# MSP-EXP430F5529LP_0.net
KiCad netlist of a schematic drawn in Altium Designer
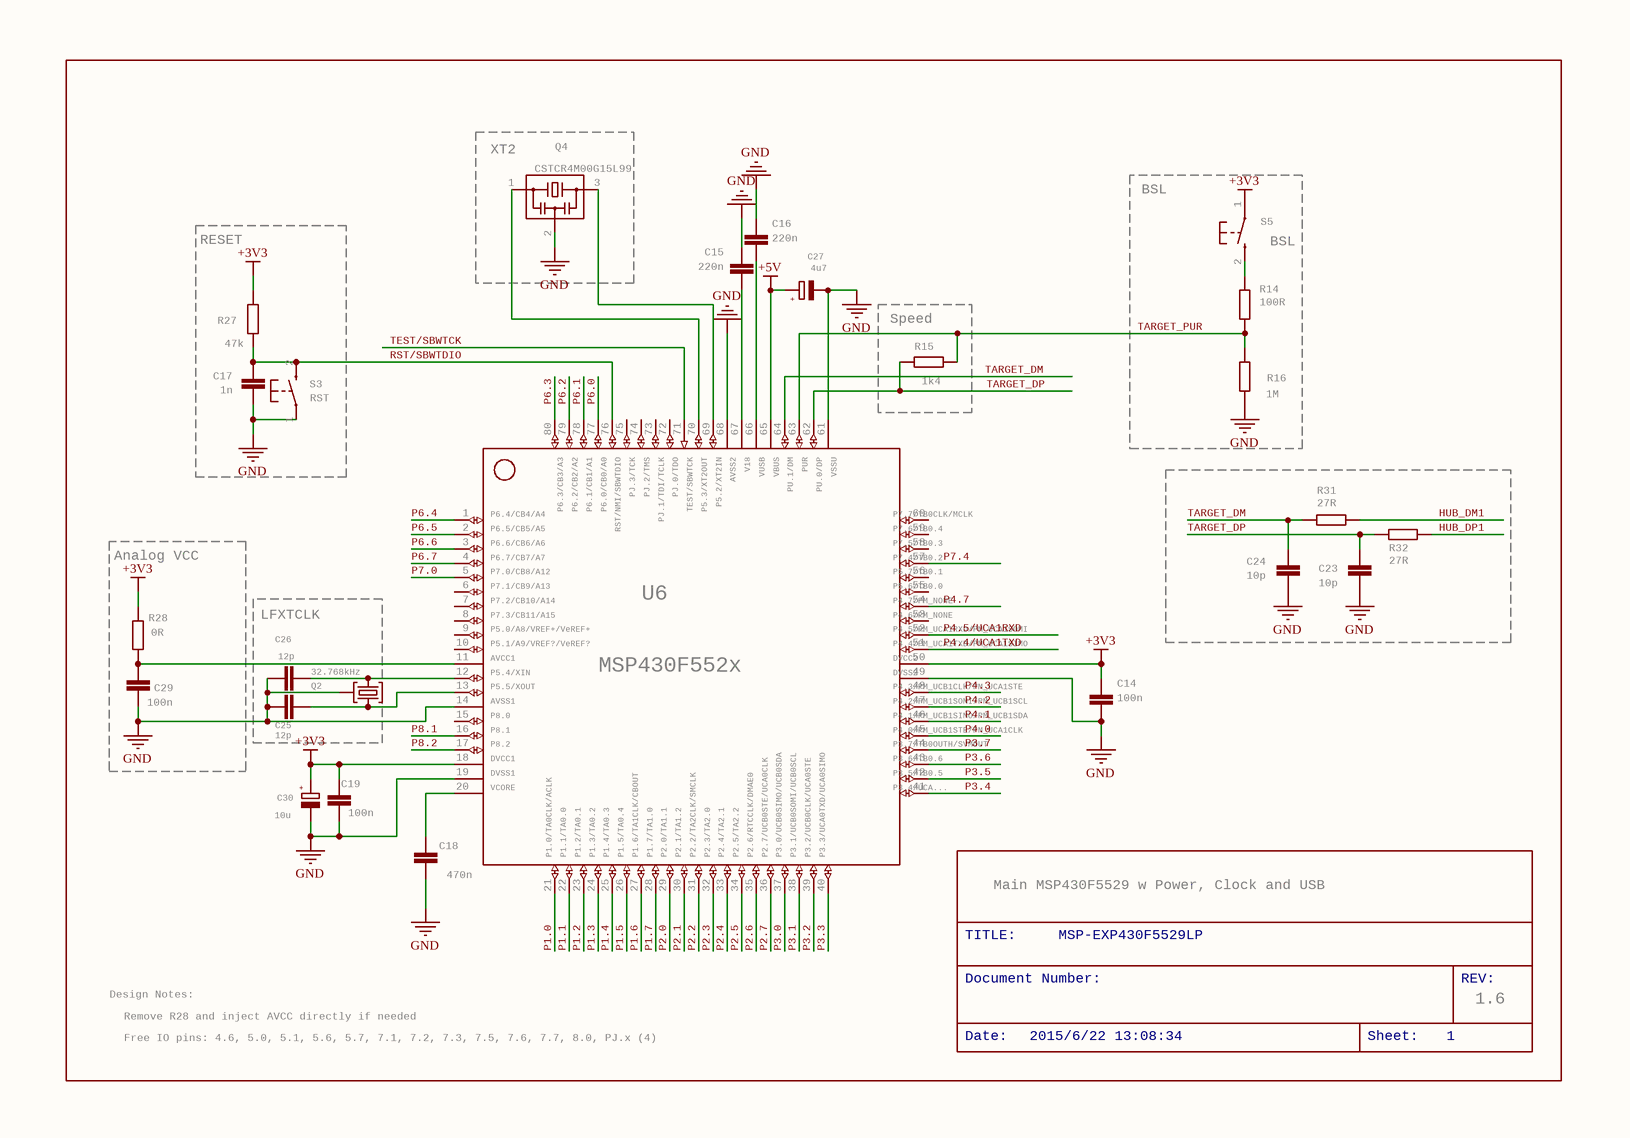
[diagram p0: MSP-EXP430F5529LP_0.SchDoc]

(export (version "E")
  (design (tool "Eeschema 10.0.6"))
  (components
    (comp (ref "C14")
      (value "100n")
      (footprint "0402")
      (description "CAPACITOR, European symbol")
      (libsource (lib "") (part "C-EUCM0402_1"))
    )
    (comp (ref "C15")
      (value "220n")
      (footprint "0402")
      (description "CAPACITOR, European symbol")
      (libsource (lib "") (part "C-EUCM0402_2"))
    )
    (comp (ref "C16")
      (value "220n")
      (footprint "0402")
      (description "CAPACITOR, European symbol")
      (libsource (lib "rcl") (part "C-EUCM0402"))
    )
    (comp (ref "C17")
      (value "1n")
      (footprint "0402")
      (description "CAPACITOR, European symbol")
      (libsource (lib "") (part "C-EUCM0402_1"))
    )
    (comp (ref "C18")
      (value "470n")
      (footprint "0402")
      (description "CAPACITOR, European symbol")
      (libsource (lib "rcl") (part "C-EUCM0402"))
    )
    (comp (ref "C19")
      (value "100n")
      (footprint "0402")
      (description "CAPACITOR, European symbol")
      (libsource (lib "rcl") (part "C-EUCM0402"))
    )
    (comp (ref "C23")
      (value "10p")
      (footprint "0402")
      (description "CAPACITOR, European symbol")
      (libsource (lib "") (part "C-EUCM0402_1"))
    )
    (comp (ref "C24")
      (value "10p")
      (footprint "0402")
      (description "CAPACITOR, European symbol")
      (libsource (lib "") (part "C-EUCM0402_1"))
    )
    (comp (ref "C25")
      (value "12p")
      (footprint "0402")
      (description "CAPACITOR, European symbol")
      (libsource (lib "") (part "C-EUCM0402_2"))
    )
    (comp (ref "C26")
      (value "12p")
      (footprint "0402")
      (description "CAPACITOR, European symbol")
      (libsource (lib "") (part "C-EUCM0402_2"))
    )
    (comp (ref "C27")
      (value "4u7")
      (footprint "A/3216-18R")
      (description "POLARIZED CAPACITOR, European symbol")
      (fields (field (name "+") "+"))
      (libsource (lib "") (part "CPOL-EUA/3216-18R_1"))
    )
    (comp (ref "C29")
      (value "100n")
      (footprint "0402")
      (description "CAPACITOR, European symbol")
      (libsource (lib "") (part "C-EUCM0402_3"))
    )
    (comp (ref "C30")
      (value "10u")
      (footprint "A/3216-18R")
      (description "POLARIZED CAPACITOR, European symbol")
      (fields (field (name "+") "+"))
      (libsource (lib "rcl") (part "CPOL-EUA/3216-18R"))
    )
    (comp (ref "Q2")
      (value "32.768kHz")
      (footprint "MS3V-T1R")
      (fields (field (name "LIBRARYNAME") "microcrystal"))
      (libsource (lib "microcrystal") (part "MS3V-T1R"))
    )
    (comp (ref "Q4")
      (value "CSTCR4M00G15L99")
      (footprint "MURATA-FILTER_CSTCR")
      (description "Resonator   Source: murata.co.jp")
      (fields (field (name "MF") "MF") (field (name "MPN") "CSTCR6M00G53-R0"))
      (libsource (lib "murata") (part "MURATA-FILTER_CSTCR"))
    )
    (comp (ref "R14")
      (value "100R")
      (footprint "0402")
      (description "RESISTOR, European symbol")
      (libsource (lib "rcl") (part "R-EU_RM0402"))
    )
    (comp (ref "R15")
      (value "1k4")
      (footprint "0402")
      (description "RESISTOR, European symbol")
      (libsource (lib "rcl") (part "R-EU_RM0402"))
    )
    (comp (ref "R16")
      (value "1M")
      (footprint "0402")
      (description "RESISTOR, European symbol")
      (libsource (lib "rcl") (part "R-EU_RM0402"))
    )
    (comp (ref "R27")
      (value "47k")
      (footprint "0402")
      (description "RESISTOR, European symbol")
      (libsource (lib "rcl") (part "R-EU_RM0402"))
    )
    (comp (ref "R28")
      (value "0R")
      (footprint "0402")
      (description "RESISTOR, European symbol")
      (libsource (lib "rcl") (part "R-EU_RM0402"))
    )
    (comp (ref "R31")
      (value "27R")
      (footprint "0402")
      (description "RESISTOR, European symbol")
      (libsource (lib "rcl") (part "R-EU_RM0402"))
    )
    (comp (ref "R32")
      (value "27R")
      (footprint "0402")
      (description "RESISTOR, European symbol")
      (libsource (lib "rcl") (part "R-EU_RM0402"))
    )
    (comp (ref "S3")
      (value "RST")
      (footprint "PBTH")
      (description "OMRON SWITCH")
      (fields (field (name "LIBRARYNAME") "electricalmeter"))
      (libsource (lib "electricalmeter") (part "PB"))
    )
    (comp (ref "S5")
      (value "BSL")
      (footprint "PBTH")
      (description "OMRON SWITCH")
      (fields (field (name "LIBRARYNAME") "electricalmeter"))
      (libsource (lib "electricalmeter") (part "PB"))
    )
    (comp (ref "U6")
      (value "MSP430F5529IPNR")
      (footprint "PN80")
      (fields
        (field (name "P6.3/CB3/A3") "P6.3/CB3/A3")
        (field (name "P6.2/CB2/A2") "P6.2/CB2/A2")
        (field (name "P6.1/CB1/A1") "P6.1/CB1/A1")
        (field (name "P6.0/CB0/A0") "P6.0/CB0/A0")
        (field (name "PJ.3/TCK") "PJ.3/TCK")
        (field (name "PJ.2/TMS") "PJ.2/TMS")
        (field (name "PJ.1/TDI/TCLK") "PJ.1/TDI/TCLK")
        (field (name "PJ.0/TDO") "PJ.0/TDO")
        (field (name "TEST/SBWTCK") "TEST/SBWTCK")
        (field (name "P5.3/XT2OUT") "P5.3/XT2OUT")
        (field (name "P5.2/XT2IN") "P5.2/XT2IN")
        (field (name "AVSS2") "AVSS2")
        (field (name "V18") "V18")
        (field (name "VUSB") "VUSB")
        (field (name "VBUS") "VBUS")
        (field (name "PU.1/DM") "PU.1/DM")
        (field (name "PUR") "PUR")
        (field (name "PU.0/DP") "PU.0/DP")
        (field (name "VSSU") "VSSU")
        (field (name "RST/NMI/SBWTDIO") "RST/NMI/SBWTDIO")
        (field (name "P7.7/TB0CLK/MCLK") "P7.7/TB0CLK/MCLK")
        (field (name "P7.6/TB0.4") "P7.6/TB0.4")
        (field (name "P7.5/TB0.3") "P7.5/TB0.3")
        (field (name "P7.4/TB0.2") "P7.4/TB0.2")
        (field (name "P5.7/TB0.1") "P5.7/TB0.1")
        (field (name "P5.6/TB0.0") "P5.6/TB0.0")
        (field (name "P4.7/PM_NONE") "P4.7/PM_NONE")
        (field (name "P4.5/PM_UCA1RXD/PM_UCA1SOMI") "P4.5/PM_UCA1RXD/PM_UCA1SOMI")
        (field (name "P4.4/PM_UCA1TXD/PM_UCA1SIMO") "P4.4/PM_UCA1TXD/PM_UCA1SIMO")
        (field (name "DVCC2") "DVCC2")
        (field (name "P4.3/PM_UCB1CLK/PM_UCA1STE") "P4.3/PM_UCB1CLK/PM_UCA1STE")
        (field (name "P4.2/PM_UCB1SOMI/PM_UCB1SCL") "P4.2/PM_UCB1SOMI/PM_UCB1SCL")
        (field (name "P4.1/PM_UCB1SIMO/PM_UCB1SDA") "P4.1/PM_UCB1SIMO/PM_UCB1SDA")
        (field (name "P4.0/PM_UCB1STE/PM_UCA1CLK") "P4.0/PM_UCB1STE/PM_UCA1CLK")
        (field (name "P3.7/TB0OUTH/SVMOUT") "P3.7/TB0OUTH/SVMOUT")
        (field (name "P3.6/TB0.6") "P3.6/TB0.6")
        (field (name "P4.6/PM_NONE") "P4.6/PM_NONE")
        (field (name "P3.5/TB0.5") "P3.5/TB0.5")
        (field (name "P3.4/UCA...") "P3.4/UCA...")
        (field (name "P1.0/TA0CLK/ACLK") "P1.0/TA0CLK/ACLK")
        (field (name "P1.1/TA0.0") "P1.1/TA0.0")
        (field (name "P1.2/TA0.1") "P1.2/TA0.1")
        (field (name "P1.3/TA0.2") "P1.3/TA0.2")
        (field (name "P1.4/TA0.3") "P1.4/TA0.3")
        (field (name "P1.5/TA0.4") "P1.5/TA0.4")
        (field (name "P1.6/TA1CLK/CBOUT") "P1.6/TA1CLK/CBOUT")
        (field (name "P1.7/TA1.0") "P1.7/TA1.0")
        (field (name "P2.0/TA1.1") "P2.0/TA1.1")
        (field (name "P2.1/TA1.2") "P2.1/TA1.2")
        (field (name "P2.2/TA2CLK/SMCLK") "P2.2/TA2CLK/SMCLK")
        (field (name "P2.4/TA2.1") "P2.4/TA2.1")
        (field (name "P2.5/TA2.2") "P2.5/TA2.2")
        (field (name "P2.6/RTCCLK/DMAE0") "P2.6/RTCCLK/DMAE0")
        (field (name "P2.7/UCB0STE/UCA0CLK") "P2.7/UCB0STE/UCA0CLK")
        (field (name "P3.0/UCB0SIMO/UCB0SDA") "P3.0/UCB0SIMO/UCB0SDA")
        (field (name "P3.1/UCB0SOMI/UCB0SCL") "P3.1/UCB0SOMI/UCB0SCL")
        (field (name "P3.2/UCB0CLK/UCA0STE") "P3.2/UCB0CLK/UCA0STE")
        (field (name "P3.3/UCA0TXD/UCA0SIMO") "P3.3/UCA0TXD/UCA0SIMO")
        (field (name "P6.4/CB4/A4") "P6.4/CB4/A4")
        (field (name "P6.5/CB5/A5") "P6.5/CB5/A5")
        (field (name "P6.6/CB6/A6") "P6.6/CB6/A6")
        (field (name "P6.7/CB7/A7") "P6.7/CB7/A7")
        (field (name "P7.0/CB8/A12") "P7.0/CB8/A12")
        (field (name "P7.1/CB9/A13") "P7.1/CB9/A13")
        (field (name "P7.2/CB10/A14") "P7.2/CB10/A14")
        (field (name "P7.3/CB11/A15") "P7.3/CB11/A15")
        (field (name "P5.0/A8/VREF+/VEREF+") "P5.0/A8/VREF+/VeREF+")
        (field (name "P5.1/A9/VREF?/VEREF?") "P5.1/A9/VREF?/VeREF?")
        (field (name "AVCC1") "AVCC1")
        (field (name "P5.4/XIN") "P5.4/XIN")
        (field (name "P5.5/XOUT") "P5.5/XOUT")
        (field (name "AVSS1") "AVSS1")
        (field (name "P8.0") "P8.0")
        (field (name "P8.1") "P8.1")
        (field (name "P8.2") "P8.2")
        (field (name "DVCC1") "DVCC1")
        (field (name "DVSS1") "DVSS1")
        (field (name "VCORE") "VCORE")
        (field (name "MSP430F552X") "MSP430F552x")
        (field (name "DVSS2") "DVSS2")
        (field (name "P2.3/TA2.0") "P2.3/TA2.0")
        (field (name "LIBRARYNAME") "TI_MSP430_v16_intern")
      )
      (libsource (lib "TI_MSP430_v16_intern") (part "F552X---PN80"))
    )
  )
  (nets
    (net (code "1") (name "+3V3") (class "Default")
      (node (ref "C14") (pin "1") (pinfunction "1_1") (pintype "passive"))
      (node (ref "C19") (pin "2") (pinfunction "2_2") (pintype "passive"))
      (node (ref "C30") (pin "+") (pinfunction "+_+") (pintype "passive"))
      (node (ref "R27") (pin "2") (pinfunction "2_2") (pintype "passive"))
      (node (ref "R28") (pin "2") (pinfunction "2_2") (pintype "passive"))
      (node (ref "S5") (pin "1") (pinfunction "P_1") (pintype "passive"))
      (node (ref "U6") (pin "18") (pinfunction "18_18") (pintype "power_in"))
      (node (ref "U6") (pin "50") (pinfunction "50_50") (pintype "power_in"))
    )
    (net (code "2") (name "+5V") (class "Default")
      (node (ref "C27") (pin "+") (pinfunction "+_+") (pintype "passive"))
      (node (ref "U6") (pin "65") (pinfunction "65_65") (pintype "power_in"))
    )
    (net (code "3") (name "/HUB_DM1") (class "Default")
      (node (ref "R31") (pin "1") (pinfunction "1_1") (pintype "passive"))
    )
    (net (code "4") (name "/HUB_DP1") (class "Default")
      (node (ref "R32") (pin "1") (pinfunction "1_1") (pintype "passive"))
    )
    (net (code "5") (name "/P1.0") (class "Default")
      (node (ref "U6") (pin "21") (pinfunction "21_21") (pintype "bidirectional"))
    )
    (net (code "6") (name "/P1.1") (class "Default")
      (node (ref "U6") (pin "22") (pinfunction "22_22") (pintype "bidirectional"))
    )
    (net (code "7") (name "/P1.2") (class "Default")
      (node (ref "U6") (pin "23") (pinfunction "23_23") (pintype "bidirectional"))
    )
    (net (code "8") (name "/P1.3") (class "Default")
      (node (ref "U6") (pin "24") (pinfunction "24_24") (pintype "bidirectional"))
    )
    (net (code "9") (name "/P1.4") (class "Default")
      (node (ref "U6") (pin "25") (pinfunction "25_25") (pintype "bidirectional"))
    )
    (net (code "10") (name "/P1.5") (class "Default")
      (node (ref "U6") (pin "26") (pinfunction "26_26") (pintype "bidirectional"))
    )
    (net (code "11") (name "/P1.6") (class "Default")
      (node (ref "U6") (pin "27") (pinfunction "27_27") (pintype "bidirectional"))
    )
    (net (code "12") (name "/P1.7") (class "Default")
      (node (ref "U6") (pin "28") (pinfunction "28_28") (pintype "bidirectional"))
    )
    (net (code "13") (name "/P2.0") (class "Default")
      (node (ref "U6") (pin "29") (pinfunction "29_29") (pintype "bidirectional"))
    )
    (net (code "14") (name "/P2.1") (class "Default")
      (node (ref "U6") (pin "30") (pinfunction "30_30") (pintype "bidirectional"))
    )
    (net (code "15") (name "/P2.2") (class "Default")
      (node (ref "U6") (pin "31") (pinfunction "31_31") (pintype "bidirectional"))
    )
    (net (code "16") (name "/P2.3") (class "Default")
      (node (ref "U6") (pin "32") (pinfunction "32_32") (pintype "bidirectional"))
    )
    (net (code "17") (name "/P2.4") (class "Default")
      (node (ref "U6") (pin "33") (pinfunction "33_33") (pintype "bidirectional"))
    )
    (net (code "18") (name "/P2.5") (class "Default")
      (node (ref "U6") (pin "34") (pinfunction "34_34") (pintype "bidirectional"))
    )
    (net (code "19") (name "/P2.6") (class "Default")
      (node (ref "U6") (pin "35") (pinfunction "35_35") (pintype "bidirectional"))
    )
    (net (code "20") (name "/P2.7") (class "Default")
      (node (ref "U6") (pin "36") (pinfunction "36_36") (pintype "bidirectional"))
    )
    (net (code "21") (name "/P3.0") (class "Default")
      (node (ref "U6") (pin "37") (pinfunction "37_37") (pintype "bidirectional"))
    )
    (net (code "22") (name "/P3.1") (class "Default")
      (node (ref "U6") (pin "38") (pinfunction "38_38") (pintype "bidirectional"))
    )
    (net (code "23") (name "/P3.2") (class "Default")
      (node (ref "U6") (pin "39") (pinfunction "39_39") (pintype "bidirectional"))
    )
    (net (code "24") (name "/P3.3") (class "Default")
      (node (ref "U6") (pin "40") (pinfunction "40_40") (pintype "bidirectional"))
    )
    (net (code "25") (name "/P3.4") (class "Default")
      (node (ref "U6") (pin "41") (pinfunction "41_41") (pintype "bidirectional"))
    )
    (net (code "26") (name "/P3.5") (class "Default")
      (node (ref "U6") (pin "42") (pinfunction "42_42") (pintype "bidirectional"))
    )
    (net (code "27") (name "/P3.6") (class "Default")
      (node (ref "U6") (pin "43") (pinfunction "43_43") (pintype "bidirectional"))
    )
    (net (code "28") (name "/P3.7") (class "Default")
      (node (ref "U6") (pin "44") (pinfunction "44_44") (pintype "bidirectional"))
    )
    (net (code "29") (name "/P4.0") (class "Default")
      (node (ref "U6") (pin "45") (pinfunction "45_45") (pintype "bidirectional"))
    )
    (net (code "30") (name "/P4.1") (class "Default")
      (node (ref "U6") (pin "46") (pinfunction "46_46") (pintype "bidirectional"))
    )
    (net (code "31") (name "/P4.2") (class "Default")
      (node (ref "U6") (pin "47") (pinfunction "47_47") (pintype "bidirectional"))
    )
    (net (code "32") (name "/P4.3") (class "Default")
      (node (ref "U6") (pin "48") (pinfunction "48_48") (pintype "bidirectional"))
    )
    (net (code "33") (name "/P4.4{slash}UCA1TXD") (class "Default")
      (node (ref "U6") (pin "51") (pinfunction "51_51") (pintype "bidirectional"))
    )
    (net (code "34") (name "/P4.5{slash}UCA1RXD") (class "Default")
      (node (ref "U6") (pin "52") (pinfunction "52_52") (pintype "bidirectional"))
    )
    (net (code "35") (name "/P4.7") (class "Default")
      (node (ref "U6") (pin "54") (pinfunction "54_54") (pintype "bidirectional"))
    )
    (net (code "36") (name "/P6.0") (class "Default")
      (node (ref "U6") (pin "77") (pinfunction "77_77") (pintype "bidirectional"))
    )
    (net (code "37") (name "/P6.1") (class "Default")
      (node (ref "U6") (pin "78") (pinfunction "78_78") (pintype "bidirectional"))
    )
    (net (code "38") (name "/P6.2") (class "Default")
      (node (ref "U6") (pin "79") (pinfunction "79_79") (pintype "bidirectional"))
    )
    (net (code "39") (name "/P6.3") (class "Default")
      (node (ref "U6") (pin "80") (pinfunction "80_80") (pintype "bidirectional"))
    )
    (net (code "40") (name "/P6.4") (class "Default")
      (node (ref "U6") (pin "1") (pinfunction "1_1") (pintype "bidirectional"))
    )
    (net (code "41") (name "/P6.5") (class "Default")
      (node (ref "U6") (pin "2") (pinfunction "2_2") (pintype "bidirectional"))
    )
    (net (code "42") (name "/P6.6") (class "Default")
      (node (ref "U6") (pin "3") (pinfunction "3_3") (pintype "bidirectional"))
    )
    (net (code "43") (name "/P6.7") (class "Default")
      (node (ref "U6") (pin "4") (pinfunction "4_4") (pintype "bidirectional"))
    )
    (net (code "44") (name "/P7.0") (class "Default")
      (node (ref "U6") (pin "5") (pinfunction "5_5") (pintype "bidirectional"))
    )
    (net (code "45") (name "/P7.4") (class "Default")
      (node (ref "U6") (pin "57") (pinfunction "57_57") (pintype "bidirectional"))
    )
    (net (code "46") (name "/P8.1") (class "Default")
      (node (ref "U6") (pin "16") (pinfunction "16_16") (pintype "bidirectional"))
    )
    (net (code "47") (name "/P8.2") (class "Default")
      (node (ref "U6") (pin "17") (pinfunction "17_17") (pintype "bidirectional"))
    )
    (net (code "48") (name "/RST{slash}SBWTDIO") (class "Default")
      (node (ref "C17") (pin "1") (pinfunction "1_1") (pintype "passive"))
      (node (ref "R27") (pin "1") (pinfunction "1_1") (pintype "passive"))
      (node (ref "S3") (pin "2") (pinfunction "S_2") (pintype "passive"))
      (node (ref "U6") (pin "76") (pinfunction "76_76") (pintype "bidirectional"))
    )
    (net (code "49") (name "/TARGET_DM") (class "Default")
      (node (ref "C24") (pin "1") (pinfunction "1_1") (pintype "passive"))
      (node (ref "R31") (pin "2") (pinfunction "2_2") (pintype "passive"))
      (node (ref "U6") (pin "64") (pinfunction "64_64") (pintype "bidirectional"))
    )
    (net (code "50") (name "/TARGET_DP") (class "Default")
      (node (ref "C23") (pin "1") (pinfunction "1_1") (pintype "passive"))
      (node (ref "R15") (pin "2") (pinfunction "2_2") (pintype "passive"))
      (node (ref "R32") (pin "2") (pinfunction "2_2") (pintype "passive"))
      (node (ref "U6") (pin "62") (pinfunction "62_62") (pintype "bidirectional"))
    )
    (net (code "51") (name "/TARGET_PUR") (class "Default")
      (node (ref "R14") (pin "2") (pinfunction "2_2") (pintype "passive"))
      (node (ref "R15") (pin "1") (pinfunction "1_1") (pintype "passive"))
      (node (ref "R16") (pin "2") (pinfunction "2_2") (pintype "passive"))
      (node (ref "U6") (pin "63") (pinfunction "63_63") (pintype "bidirectional"))
    )
    (net (code "52") (name "/TEST{slash}SBWTCK") (class "Default")
      (node (ref "U6") (pin "71") (pinfunction "71_71") (pintype "input"))
    )
    (net (code "53") (name "GND") (class "Default")
      (node (ref "C14") (pin "2") (pinfunction "2_2") (pintype "passive"))
      (node (ref "C15") (pin "2") (pinfunction "2_2") (pintype "passive"))
      (node (ref "C16") (pin "2") (pinfunction "2_2") (pintype "passive"))
      (node (ref "C17") (pin "2") (pinfunction "2_2") (pintype "passive"))
      (node (ref "C18") (pin "1") (pinfunction "1_1") (pintype "passive"))
      (node (ref "C19") (pin "1") (pinfunction "1_1") (pintype "passive"))
      (node (ref "C23") (pin "2") (pinfunction "2_2") (pintype "passive"))
      (node (ref "C24") (pin "2") (pinfunction "2_2") (pintype "passive"))
      (node (ref "C25") (pin "1") (pinfunction "1_1") (pintype "passive"))
      (node (ref "C26") (pin "1") (pinfunction "1_1") (pintype "passive"))
      (node (ref "C27") (pin "-") (pinfunction "-_-") (pintype "passive"))
      (node (ref "C29") (pin "2") (pinfunction "2_2") (pintype "passive"))
      (node (ref "C30") (pin "-") (pinfunction "-_-") (pintype "passive"))
      (node (ref "Q2") (pin "P3") (pinfunction "GND_P3") (pintype "power_in"))
      (node (ref "Q4") (pin "2") (pinfunction "2_2") (pintype "passive"))
      (node (ref "R16") (pin "1") (pinfunction "1_1") (pintype "passive"))
      (node (ref "S3") (pin "1") (pinfunction "P_1") (pintype "passive"))
      (node (ref "U6") (pin "14") (pinfunction "14_14") (pintype "power_in"))
      (node (ref "U6") (pin "19") (pinfunction "19_19") (pintype "power_in"))
      (node (ref "U6") (pin "49") (pinfunction "49_49") (pintype "power_in"))
      (node (ref "U6") (pin "61") (pinfunction "61_61") (pintype "power_in"))
      (node (ref "U6") (pin "68") (pinfunction "68_68") (pintype "power_in"))
    )
    (net (code "54") (name "Net-(C15-Pad1)") (class "Default")
      (node (ref "C15") (pin "1") (pinfunction "1_1") (pintype "passive"))
      (node (ref "U6") (pin "67") (pinfunction "67_67") (pintype "power_in"))
    )
    (net (code "55") (name "Net-(C16-Pad1)") (class "Default")
      (node (ref "C16") (pin "1") (pinfunction "1_1") (pintype "passive"))
      (node (ref "U6") (pin "66") (pinfunction "66_66") (pintype "power_in"))
    )
    (net (code "56") (name "Net-(C18-Pad2)") (class "Default")
      (node (ref "C18") (pin "2") (pinfunction "2_2") (pintype "passive"))
      (node (ref "U6") (pin "20") (pinfunction "20_20") (pintype "power_in"))
    )
    (net (code "57") (name "Net-(C29-Pad1)") (class "Default")
      (node (ref "C29") (pin "1") (pinfunction "1_1") (pintype "passive"))
      (node (ref "R28") (pin "1") (pinfunction "1_1") (pintype "passive"))
      (node (ref "U6") (pin "11") (pinfunction "11_11") (pintype "power_in"))
    )
    (net (code "58") (name "Net-(Q2-1)") (class "Default")
      (node (ref "C25") (pin "2") (pinfunction "2_2") (pintype "passive"))
      (node (ref "Q2") (pin "P1") (pinfunction "1_P1") (pintype "bidirectional"))
      (node (ref "U6") (pin "13") (pinfunction "13_13") (pintype "bidirectional"))
    )
    (net (code "59") (name "Net-(Q2-2)") (class "Default")
      (node (ref "C26") (pin "2") (pinfunction "2_2") (pintype "passive"))
      (node (ref "Q2") (pin "P2") (pinfunction "2_P2") (pintype "bidirectional"))
      (node (ref "U6") (pin "12") (pinfunction "12_12") (pintype "bidirectional"))
    )
    (net (code "60") (name "Net-(Q4-Pad1)") (class "Default")
      (node (ref "Q4") (pin "1") (pinfunction "1_1") (pintype "passive"))
      (node (ref "U6") (pin "70") (pinfunction "70_70") (pintype "bidirectional"))
    )
    (net (code "61") (name "Net-(Q4-Pad3)") (class "Default")
      (node (ref "Q4") (pin "3") (pinfunction "3_3") (pintype "passive"))
      (node (ref "U6") (pin "69") (pinfunction "69_69") (pintype "bidirectional"))
    )
    (net (code "62") (name "Net-(S5-S)") (class "Default")
      (node (ref "R14") (pin "1") (pinfunction "1_1") (pintype "passive"))
      (node (ref "S5") (pin "2") (pinfunction "S_2") (pintype "passive"))
    )
    (net (code "63") (name "unconnected-(U6-Pad6)") (class "Default")
      (node (ref "U6") (pin "6") (pinfunction "6_6") (pintype "bidirectional"))
    )
    (net (code "64") (name "unconnected-(U6-Pad7)") (class "Default")
      (node (ref "U6") (pin "7") (pinfunction "7_7") (pintype "bidirectional"))
    )
    (net (code "65") (name "unconnected-(U6-Pad8)") (class "Default")
      (node (ref "U6") (pin "8") (pinfunction "8_8") (pintype "bidirectional"))
    )
    (net (code "66") (name "unconnected-(U6-Pad9)") (class "Default")
      (node (ref "U6") (pin "9") (pinfunction "9_9") (pintype "bidirectional"))
    )
    (net (code "67") (name "unconnected-(U6-Pad10)") (class "Default")
      (node (ref "U6") (pin "10") (pinfunction "10_10") (pintype "bidirectional"))
    )
    (net (code "68") (name "unconnected-(U6-Pad15)") (class "Default")
      (node (ref "U6") (pin "15") (pinfunction "15_15") (pintype "bidirectional"))
    )
    (net (code "69") (name "unconnected-(U6-Pad53)") (class "Default")
      (node (ref "U6") (pin "53") (pinfunction "53_53") (pintype "bidirectional"))
    )
    (net (code "70") (name "unconnected-(U6-Pad55)") (class "Default")
      (node (ref "U6") (pin "55") (pinfunction "55_55") (pintype "bidirectional"))
    )
    (net (code "71") (name "unconnected-(U6-Pad56)") (class "Default")
      (node (ref "U6") (pin "56") (pinfunction "56_56") (pintype "bidirectional"))
    )
    (net (code "72") (name "unconnected-(U6-Pad58)") (class "Default")
      (node (ref "U6") (pin "58") (pinfunction "58_58") (pintype "bidirectional"))
    )
    (net (code "73") (name "unconnected-(U6-Pad59)") (class "Default")
      (node (ref "U6") (pin "59") (pinfunction "59_59") (pintype "bidirectional"))
    )
    (net (code "74") (name "unconnected-(U6-Pad60)") (class "Default")
      (node (ref "U6") (pin "60") (pinfunction "60_60") (pintype "bidirectional"))
    )
    (net (code "75") (name "unconnected-(U6-Pad72)") (class "Default")
      (node (ref "U6") (pin "72") (pinfunction "72_72") (pintype "bidirectional"))
    )
    (net (code "76") (name "unconnected-(U6-Pad73)") (class "Default")
      (node (ref "U6") (pin "73") (pinfunction "73_73") (pintype "bidirectional"))
    )
    (net (code "77") (name "unconnected-(U6-Pad74)") (class "Default")
      (node (ref "U6") (pin "74") (pinfunction "74_74") (pintype "bidirectional"))
    )
    (net (code "78") (name "unconnected-(U6-Pad75)") (class "Default")
      (node (ref "U6") (pin "75") (pinfunction "75_75") (pintype "bidirectional"))
    )
  )
)
